# zxld381-boost-driver-12mm-mk-1.net
KiCad netlist of a schematic drawn in EAGLE
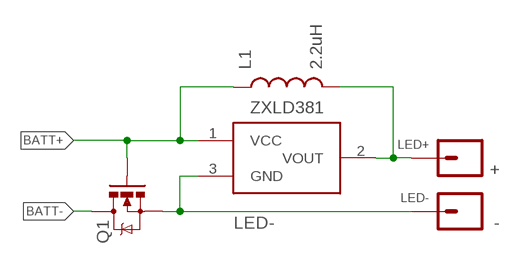
[diagram p0: schematic, sheet 1]

(export (version "E")
  (design (tool "Eeschema 10.0.6"))
  (components
    (comp (ref "+")
      (value "M01PTH-NS-NOTSUCK")
      (footprint "eagle-import:1X01NSATALL")
      (libsource (lib "eagle-import") (part "M01PTH-NS-NOTSUCK"))
    )
    (comp (ref "-")
      (value "M01PTH-NS-NOTSUCK")
      (footprint "eagle-import:1X01NSATALL")
      (libsource (lib "eagle-import") (part "M01PTH-NS-NOTSUCK"))
    )
    (comp (ref "L1")
      (value "2.2uH")
      (footprint "eagle-import:0805")
      (libsource (lib "eagle-import") (part "INDUCTOR0805"))
    )
    (comp (ref "Q1")
      (value "MOSFET-NCHANNELIRLML2502")
      (footprint "eagle-import:SOT23")
      (libsource (lib "eagle-import") (part "MOSFET-NCHANNELIRLML2502"))
    )
    (comp (ref "ZXLD381")
      (value "ZXLD381")
      (footprint "eagle-import:SOT23-3")
      (libsource (lib "eagle-import") (part "ZXLD381"))
    )
  )
  (nets
    (net (code "1") (name "/LED+") (class "Default")
      (node (ref "+") (pin "1") (pinfunction "1_1") (pintype "passive"))
      (node (ref "L1") (pin "2") (pinfunction "2_2") (pintype "passive"))
      (node (ref "ZXLD381") (pin "2") (pinfunction "VOUT_2") (pintype "bidirectional"))
    )
    (net (code "2") (name "/LED-") (class "Default")
      (node (ref "-") (pin "1") (pinfunction "1_1") (pintype "passive"))
      (node (ref "Q1") (pin "2") (pinfunction "S_2") (pintype "passive"))
      (node (ref "ZXLD381") (pin "3") (pinfunction "GND_3") (pintype "bidirectional"))
    )
    (net (code "3") (name "BATT+") (class "Default")
      (node (ref "L1") (pin "1") (pinfunction "1_1") (pintype "passive"))
      (node (ref "Q1") (pin "1") (pinfunction "G_1") (pintype "passive"))
      (node (ref "ZXLD381") (pin "1") (pinfunction "VCC_1") (pintype "bidirectional"))
    )
    (net (code "4") (name "BATT-") (class "Default")
      (node (ref "Q1") (pin "3") (pinfunction "D_3") (pintype "passive"))
    )
  )
)
